# picboard.net
KiCad netlist of a schematic drawn in EAGLE
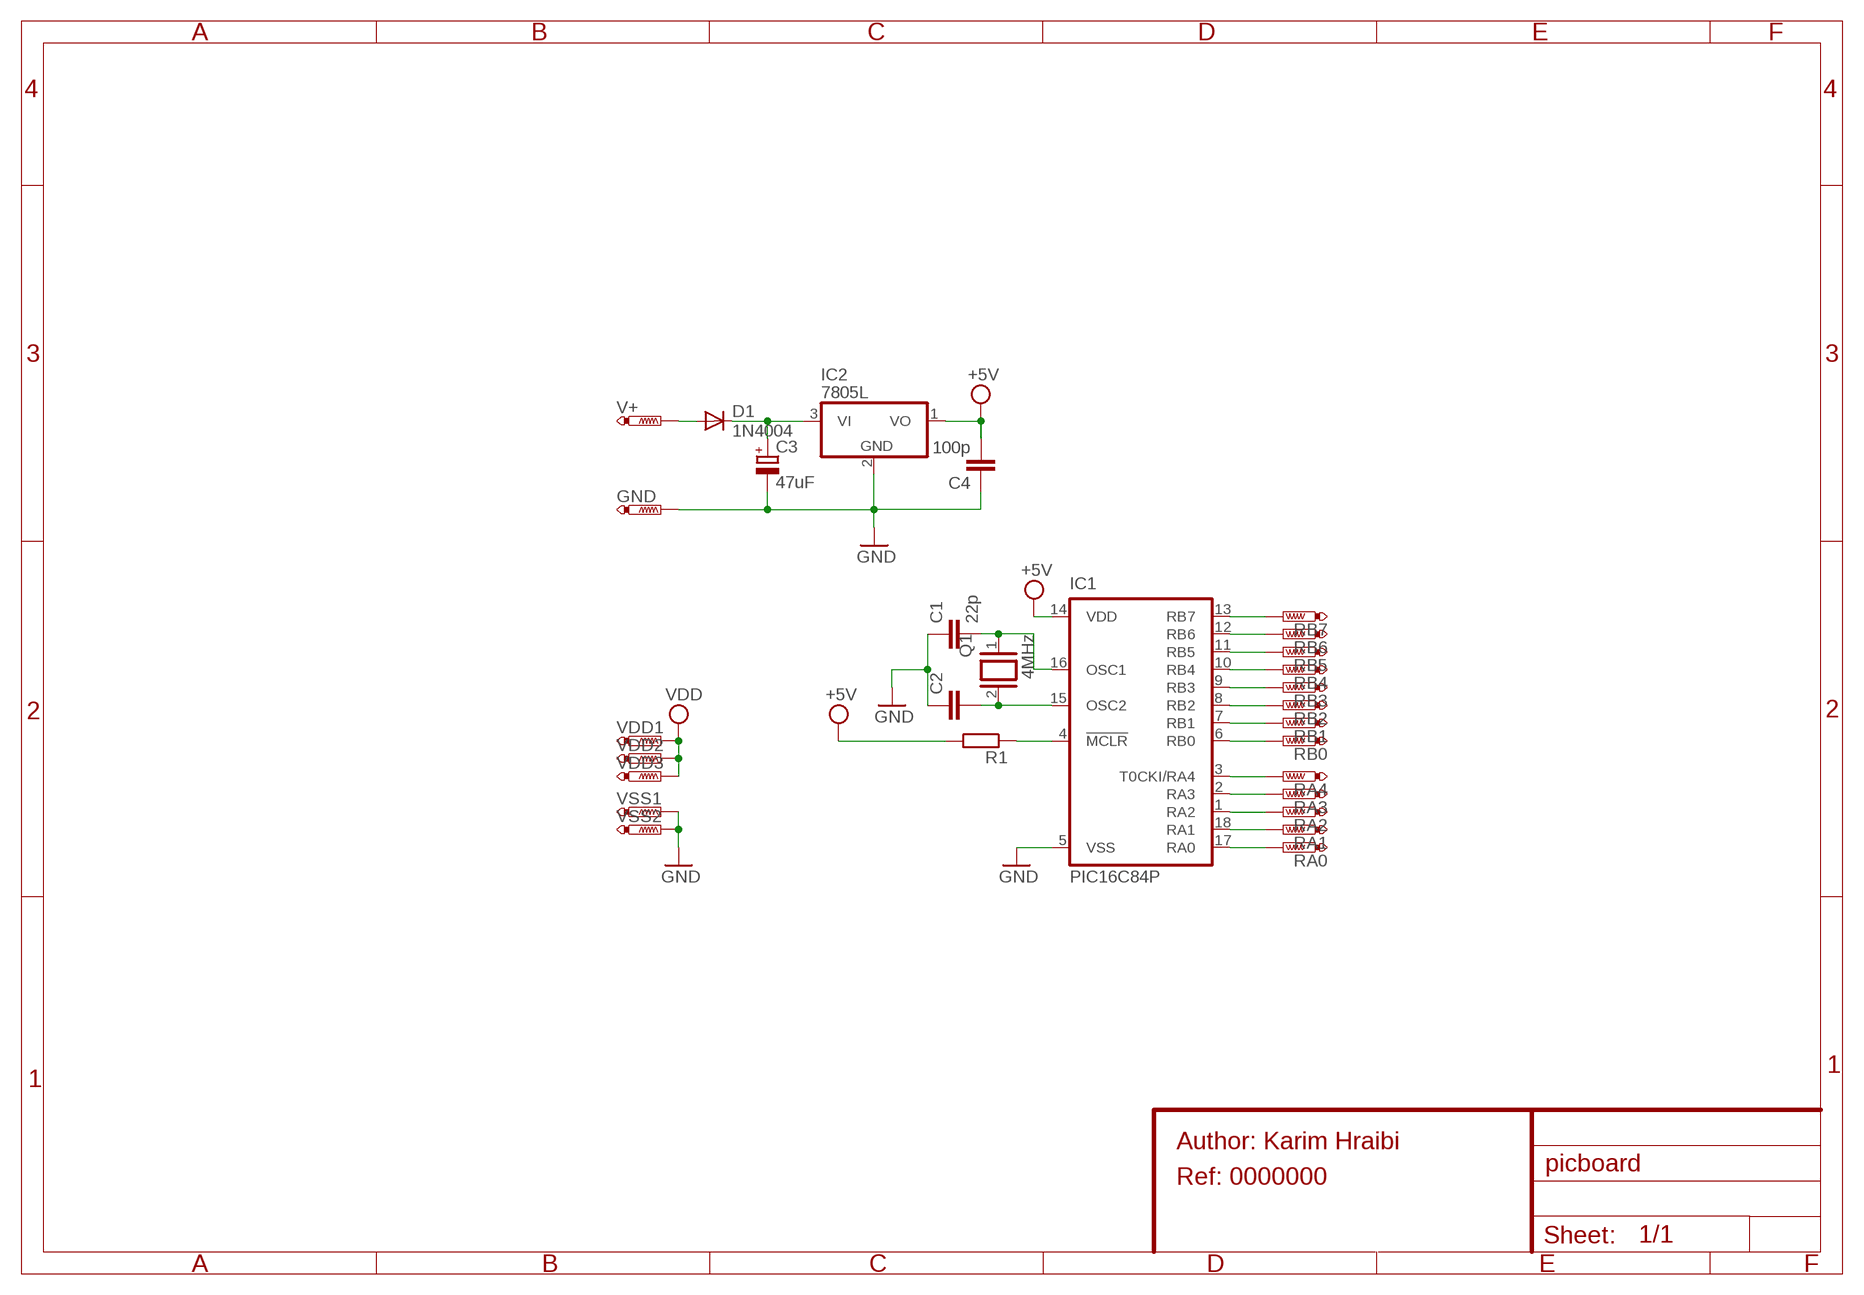
[diagram p0: schematic, sheet 1]

(export (version "E")
  (design (tool "Eeschema 10.0.6"))
  (components
    (comp (ref "C1")
      (value "22p")
      (footprint "eagle-import:C025-025X050")
      (libsource (lib "eagle-import") (part "C-EU025-025X050"))
    )
    (comp (ref "C2")
      (value "C-EU025-025X050")
      (footprint "eagle-import:C025-025X050")
      (libsource (lib "eagle-import") (part "C-EU025-025X050"))
    )
    (comp (ref "C3")
      (value "47uF")
      (footprint "eagle-import:E2,5-5")
      (libsource (lib "eagle-import") (part "CPOL-EUE2.5-5"))
    )
    (comp (ref "C4")
      (value "100p")
      (footprint "eagle-import:C025-025X050")
      (libsource (lib "eagle-import") (part "C-EU025-025X050"))
    )
    (comp (ref "D1")
      (value "1N4004")
      (footprint "eagle-import:DO41-10")
      (libsource (lib "eagle-import") (part "1N4004"))
    )
    (comp (ref "GND")
      (value "PTR1PAD1")
      (footprint "eagle-import:P1")
      (libsource (lib "eagle-import") (part "PTR1PAD1"))
    )
    (comp (ref "IC1")
      (value "PIC16C84P")
      (footprint "eagle-import:DIL18")
      (libsource (lib "eagle-import") (part "PIC16C84P"))
    )
    (comp (ref "IC2")
      (value "7805L")
      (footprint "eagle-import:TO92")
      (libsource (lib "eagle-import") (part "78L05"))
    )
    (comp (ref "Q1")
      (value "4MHz")
      (footprint "eagle-import:QS")
      (libsource (lib "eagle-import") (part "XTAL/S"))
    )
    (comp (ref "R1")
      (value "R-EU_0207/2V")
      (footprint "eagle-import:0207_2V")
      (libsource (lib "eagle-import") (part "R-EU_0207/2V"))
    )
    (comp (ref "RA0")
      (value "PTR1PAD1")
      (footprint "eagle-import:P1")
      (libsource (lib "eagle-import") (part "PTR1PAD1"))
    )
    (comp (ref "RA1")
      (value "PTR1PAD1")
      (footprint "eagle-import:P1")
      (libsource (lib "eagle-import") (part "PTR1PAD1"))
    )
    (comp (ref "RA2")
      (value "PTR1PAD1")
      (footprint "eagle-import:P1")
      (libsource (lib "eagle-import") (part "PTR1PAD1"))
    )
    (comp (ref "RA3")
      (value "PTR1PAD1")
      (footprint "eagle-import:P1")
      (libsource (lib "eagle-import") (part "PTR1PAD1"))
    )
    (comp (ref "RA4")
      (value "PTR1PAD1")
      (footprint "eagle-import:P1")
      (libsource (lib "eagle-import") (part "PTR1PAD1"))
    )
    (comp (ref "RB0")
      (value "PTR1PAD1")
      (footprint "eagle-import:P1")
      (libsource (lib "eagle-import") (part "PTR1PAD1"))
    )
    (comp (ref "RB1")
      (value "PTR1PAD1")
      (footprint "eagle-import:P1")
      (libsource (lib "eagle-import") (part "PTR1PAD1"))
    )
    (comp (ref "RB2")
      (value "PTR1PAD1")
      (footprint "eagle-import:P1")
      (libsource (lib "eagle-import") (part "PTR1PAD1"))
    )
    (comp (ref "RB3")
      (value "PTR1PAD1")
      (footprint "eagle-import:P1")
      (libsource (lib "eagle-import") (part "PTR1PAD1"))
    )
    (comp (ref "RB4")
      (value "PTR1PAD1")
      (footprint "eagle-import:P1")
      (libsource (lib "eagle-import") (part "PTR1PAD1"))
    )
    (comp (ref "RB5")
      (value "PTR1PAD1")
      (footprint "eagle-import:P1")
      (libsource (lib "eagle-import") (part "PTR1PAD1"))
    )
    (comp (ref "RB6")
      (value "PTR1PAD1")
      (footprint "eagle-import:P1")
      (libsource (lib "eagle-import") (part "PTR1PAD1"))
    )
    (comp (ref "RB7")
      (value "PTR1PAD1")
      (footprint "eagle-import:P1")
      (libsource (lib "eagle-import") (part "PTR1PAD1"))
    )
    (comp (ref "V+")
      (value "PTR1PAD1")
      (footprint "eagle-import:P1")
      (libsource (lib "eagle-import") (part "PTR1PAD1"))
    )
    (comp (ref "VDD1")
      (value "PTR1PAD1")
      (footprint "eagle-import:P1")
      (libsource (lib "eagle-import") (part "PTR1PAD1"))
    )
    (comp (ref "VDD2")
      (value "PTR1PAD1")
      (footprint "eagle-import:P1")
      (libsource (lib "eagle-import") (part "PTR1PAD1"))
    )
    (comp (ref "VDD3")
      (value "PTR1PAD1")
      (footprint "eagle-import:P1")
      (libsource (lib "eagle-import") (part "PTR1PAD1"))
    )
    (comp (ref "VSS1")
      (value "PTR1PAD1")
      (footprint "eagle-import:P1")
      (libsource (lib "eagle-import") (part "PTR1PAD1"))
    )
    (comp (ref "VSS2")
      (value "PTR1PAD1")
      (footprint "eagle-import:P1")
      (libsource (lib "eagle-import") (part "PTR1PAD1"))
    )
  )
  (nets
    (net (code "1") (name "+5V") (class "Default")
      (node (ref "C4") (pin "2") (pinfunction "2_2") (pintype "passive"))
      (node (ref "IC1") (pin "14") (pinfunction "VDD_14") (pintype "power_in"))
      (node (ref "IC2") (pin "1") (pinfunction "VO_1") (pintype "passive"))
      (node (ref "R1") (pin "2") (pinfunction "2_2") (pintype "passive"))
      (node (ref "VDD1") (pin "P$1") (pinfunction "TP_P$1") (pintype "input"))
      (node (ref "VDD2") (pin "P$1") (pinfunction "TP_P$1") (pintype "input"))
      (node (ref "VDD3") (pin "P$1") (pinfunction "TP_P$1") (pintype "input"))
    )
    (net (code "2") (name "GND") (class "Default")
      (node (ref "C1") (pin "1") (pinfunction "1_1") (pintype "passive"))
      (node (ref "C2") (pin "1") (pinfunction "1_1") (pintype "passive"))
      (node (ref "C3") (pin "-") (pinfunction "-_-") (pintype "passive"))
      (node (ref "C4") (pin "1") (pinfunction "1_1") (pintype "passive"))
      (node (ref "GND") (pin "P$1") (pinfunction "TP_P$1") (pintype "input"))
      (node (ref "IC1") (pin "5") (pinfunction "VSS_5") (pintype "power_in"))
      (node (ref "IC2") (pin "2") (pinfunction "GND_2") (pintype "passive"))
      (node (ref "VSS1") (pin "P$1") (pinfunction "TP_P$1") (pintype "input"))
      (node (ref "VSS2") (pin "P$1") (pinfunction "TP_P$1") (pintype "input"))
    )
    (net (code "3") (name "Net-(IC1-OSC1)") (class "Default")
      (node (ref "C1") (pin "2") (pinfunction "2_2") (pintype "passive"))
      (node (ref "IC1") (pin "16") (pinfunction "OSC1_16") (pintype "input"))
      (node (ref "Q1") (pin "1") (pinfunction "1_1") (pintype "passive"))
    )
    (net (code "4") (name "Net-(IC1-OSC2)") (class "Default")
      (node (ref "C2") (pin "2") (pinfunction "2_2") (pintype "passive"))
      (node (ref "IC1") (pin "15") (pinfunction "OSC2_15") (pintype "output"))
      (node (ref "Q1") (pin "2") (pinfunction "2_2") (pintype "passive"))
    )
    (net (code "5") (name "Net-(IC1-RA0)") (class "Default")
      (node (ref "IC1") (pin "17") (pinfunction "RA0_17") (pintype "bidirectional"))
      (node (ref "RA0") (pin "P$1") (pinfunction "TP_P$1") (pintype "input"))
    )
    (net (code "6") (name "Net-(IC1-RA1)") (class "Default")
      (node (ref "IC1") (pin "18") (pinfunction "RA1_18") (pintype "bidirectional"))
      (node (ref "RA1") (pin "P$1") (pinfunction "TP_P$1") (pintype "input"))
    )
    (net (code "7") (name "Net-(IC1-RA2)") (class "Default")
      (node (ref "IC1") (pin "1") (pinfunction "RA2_1") (pintype "bidirectional"))
      (node (ref "RA2") (pin "P$1") (pinfunction "TP_P$1") (pintype "input"))
    )
    (net (code "8") (name "Net-(IC1-RA3)") (class "Default")
      (node (ref "IC1") (pin "2") (pinfunction "RA3_2") (pintype "bidirectional"))
      (node (ref "RA3") (pin "P$1") (pinfunction "TP_P$1") (pintype "input"))
    )
    (net (code "9") (name "Net-(IC1-RB0)") (class "Default")
      (node (ref "IC1") (pin "6") (pinfunction "RB0_6") (pintype "bidirectional"))
      (node (ref "RB0") (pin "P$1") (pinfunction "TP_P$1") (pintype "input"))
    )
    (net (code "10") (name "Net-(IC1-RB1)") (class "Default")
      (node (ref "IC1") (pin "7") (pinfunction "RB1_7") (pintype "bidirectional"))
      (node (ref "RB1") (pin "P$1") (pinfunction "TP_P$1") (pintype "input"))
    )
    (net (code "11") (name "Net-(IC1-RB2)") (class "Default")
      (node (ref "IC1") (pin "8") (pinfunction "RB2_8") (pintype "bidirectional"))
      (node (ref "RB2") (pin "P$1") (pinfunction "TP_P$1") (pintype "input"))
    )
    (net (code "12") (name "Net-(IC1-RB3)") (class "Default")
      (node (ref "IC1") (pin "9") (pinfunction "RB3_9") (pintype "bidirectional"))
      (node (ref "RB3") (pin "P$1") (pinfunction "TP_P$1") (pintype "input"))
    )
    (net (code "13") (name "Net-(IC1-RB4)") (class "Default")
      (node (ref "IC1") (pin "10") (pinfunction "RB4_10") (pintype "bidirectional"))
      (node (ref "RB4") (pin "P$1") (pinfunction "TP_P$1") (pintype "input"))
    )
    (net (code "14") (name "Net-(IC1-RB5)") (class "Default")
      (node (ref "IC1") (pin "11") (pinfunction "RB5_11") (pintype "bidirectional"))
      (node (ref "RB5") (pin "P$1") (pinfunction "TP_P$1") (pintype "input"))
    )
    (net (code "15") (name "Net-(IC1-RB6)") (class "Default")
      (node (ref "IC1") (pin "12") (pinfunction "RB6_12") (pintype "bidirectional"))
      (node (ref "RB6") (pin "P$1") (pinfunction "TP_P$1") (pintype "input"))
    )
    (net (code "16") (name "Net-(IC1-RB7)") (class "Default")
      (node (ref "IC1") (pin "13") (pinfunction "RB7_13") (pintype "bidirectional"))
      (node (ref "RB7") (pin "P$1") (pinfunction "TP_P$1") (pintype "input"))
    )
    (net (code "17") (name "Net-(IC1-T0CKI{slash}RA4)") (class "Default")
      (node (ref "IC1") (pin "3") (pinfunction "T0CKI/RA4_3") (pintype "bidirectional"))
      (node (ref "RA4") (pin "P$1") (pinfunction "TP_P$1") (pintype "input"))
    )
    (net (code "18") (name "Net-(IC1-~{MCLR})") (class "Default")
      (node (ref "IC1") (pin "4") (pinfunction "~{MCLR}_4") (pintype "input"))
      (node (ref "R1") (pin "1") (pinfunction "1_1") (pintype "passive"))
    )
    (net (code "19") (name "Net-(IC2-VI)") (class "Default")
      (node (ref "C3") (pin "+") (pinfunction "+_+") (pintype "passive"))
      (node (ref "D1") (pin "C") (pinfunction "C_C") (pintype "passive"))
      (node (ref "IC2") (pin "3") (pinfunction "VI_3") (pintype "input"))
    )
    (net (code "20") (name "Net-(V+-TP)") (class "Default")
      (node (ref "D1") (pin "A") (pinfunction "A_A") (pintype "passive"))
      (node (ref "V+") (pin "P$1") (pinfunction "TP_P$1") (pintype "input"))
    )
  )
)
